# Proiect_TSC_v66.net
KiCad netlist of a schematic drawn in EAGLE
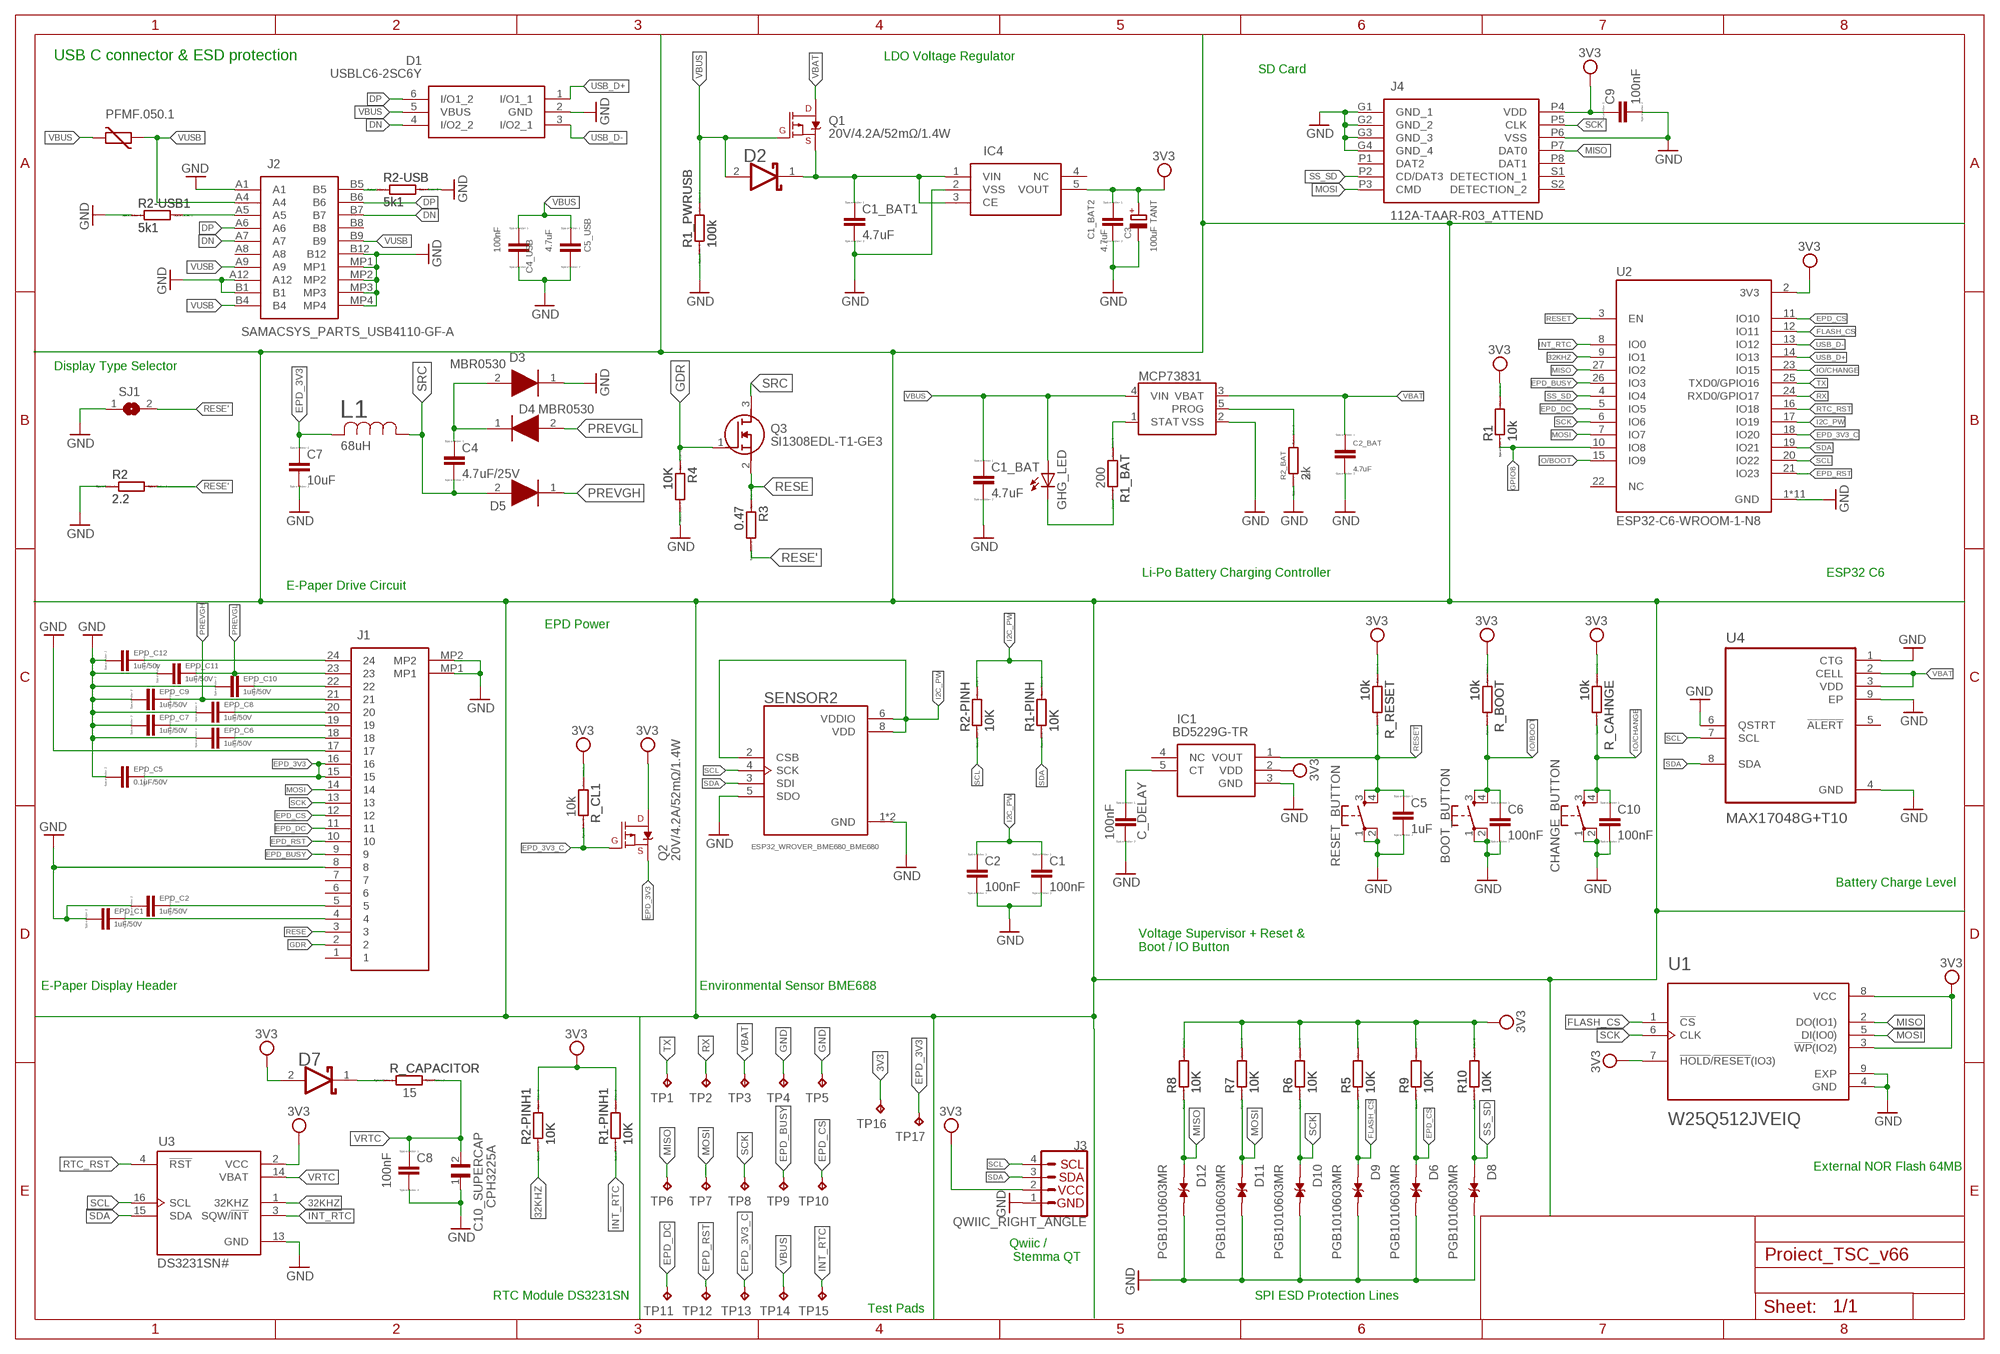
[diagram p0: schematic, sheet 1]

(export (version "E")
  (design (tool "Eeschema 10.0.6"))
  (components
    (comp (ref "BOOT_BUTTON")
      (value "BUTTON_CUSYOMV1")
      (footprint "eagle-import:MYBUTTON")
      (libsource (lib "eagle-import") (part "BUTTON_CUSYOMV1"))
    )
    (comp (ref "C1")
      (value "100nF")
      (footprint "eagle-import:EAGLE-LTSPICE_C0402")
      (libsource (lib "eagle-import") (part "EAGLE-LTSPICE_CC0402"))
    )
    (comp (ref "C1_BAT")
      (value "4.7uF")
      (footprint "eagle-import:ESP32_WROVER_EAGLE-LTSPICE_C0402")
      (libsource (lib "eagle-import") (part "ESP32_WROVER_EAGLE-LTSPICE_CC0402"))
    )
    (comp (ref "C1_BAT1")
      (value "4.7uF")
      (footprint "eagle-import:EAGLE-LTSPICE_C0402")
      (libsource (lib "eagle-import") (part "EAGLE-LTSPICE_CC0402"))
    )
    (comp (ref "C1_BAT2")
      (value "4.7uF")
      (footprint "eagle-import:EAGLE-LTSPICE_C0402")
      (libsource (lib "eagle-import") (part "EAGLE-LTSPICE_CC0402"))
    )
    (comp (ref "C2")
      (value "100nF")
      (footprint "eagle-import:EAGLE-LTSPICE_C0402")
      (libsource (lib "eagle-import") (part "EAGLE-LTSPICE_CC0402"))
    )
    (comp (ref "C2_BAT")
      (value "4.7uF")
      (footprint "eagle-import:ESP32_WROVER_EAGLE-LTSPICE_C0402")
      (libsource (lib "eagle-import") (part "ESP32_WROVER_EAGLE-LTSPICE_CC0402"))
    )
    (comp (ref "C3")
      (value "100uF TANT")
      (footprint "eagle-import:RCL_CT3528")
      (libsource (lib "eagle-import") (part "RCL_CPOL-EUCT3528"))
    )
    (comp (ref "C4")
      (value "4.7uF/25V")
      (footprint "eagle-import:ESP32_WROVER_EAGLE-LTSPICE_C0402")
      (libsource (lib "eagle-import") (part "ESP32_WROVER_EAGLE-LTSPICE_CC0402"))
    )
    (comp (ref "C4_USB")
      (value "100nF")
      (footprint "eagle-import:ESP32_WROVER_EAGLE-LTSPICE_C0402")
      (libsource (lib "eagle-import") (part "ESP32_WROVER_EAGLE-LTSPICE_CC0402"))
    )
    (comp (ref "C5")
      (value "1uF")
      (footprint "eagle-import:ESP32_WROVER_EAGLE-LTSPICE_C0402")
      (libsource (lib "eagle-import") (part "ESP32_WROVER_EAGLE-LTSPICE_CC0402"))
    )
    (comp (ref "C5_USB")
      (value "4.7uF")
      (footprint "eagle-import:ESP32_WROVER_EAGLE-LTSPICE_C0402")
      (libsource (lib "eagle-import") (part "ESP32_WROVER_EAGLE-LTSPICE_CC0402"))
    )
    (comp (ref "C6")
      (value "100nF")
      (footprint "eagle-import:ESP32_WROVER_EAGLE-LTSPICE_C0402")
      (libsource (lib "eagle-import") (part "ESP32_WROVER_EAGLE-LTSPICE_CC0402"))
    )
    (comp (ref "C7")
      (value "10uF")
      (footprint "eagle-import:EAGLE-LTSPICE_C0402")
      (libsource (lib "eagle-import") (part "EAGLE-LTSPICE_CC0402"))
    )
    (comp (ref "C8")
      (value "100nF")
      (footprint "eagle-import:ESP32_WROVER_EAGLE-LTSPICE_C0402")
      (libsource (lib "eagle-import") (part "ESP32_WROVER_EAGLE-LTSPICE_CC0402"))
    )
    (comp (ref "C9")
      (value "100nF")
      (footprint "eagle-import:EAGLE-LTSPICE_C0402")
      (libsource (lib "eagle-import") (part "EAGLE-LTSPICE_CC0402"))
    )
    (comp (ref "C10")
      (value "100nF")
      (footprint "eagle-import:ESP32_WROVER_EAGLE-LTSPICE_C0402")
      (libsource (lib "eagle-import") (part "ESP32_WROVER_EAGLE-LTSPICE_CC0402"))
    )
    (comp (ref "C10_SUPERCAP")
      (value "CPH3225A")
      (footprint "eagle-import:CAPCP3225X100N")
      (fields (field (name "MF") "Seiko Instruments"))
      (libsource (lib "eagle-import") (part "CPH3225A"))
    )
    (comp (ref "CHANGE_BUTTON")
      (value "BUTTON_CUSYOMV1")
      (footprint "eagle-import:MYBUTTON")
      (libsource (lib "eagle-import") (part "BUTTON_CUSYOMV1"))
    )
    (comp (ref "C_DELAY")
      (value "100nF")
      (footprint "eagle-import:EAGLE-LTSPICE_C0402")
      (libsource (lib "eagle-import") (part "EAGLE-LTSPICE_CC0402"))
    )
    (comp (ref "D1")
      (value "USBLC6-2SC6Y")
      (footprint "eagle-import:SOT95P280X145-6N")
      (fields (field (name "MF") "STMicroelectronics"))
      (libsource (lib "eagle-import") (part "USBLC6-2SC6Y"))
    )
    (comp (ref "D2")
      (value "ESP32_WROVER_AVX---SD0805S020S1R0_AVX_SD0805S020S1R0_0_0AVX_SD0805S020S1R0_0_0")
      (footprint "eagle-import:ESP32_WROVER_AVX---SD0805S020S1R0_AVX_SD0805S020S1R0_0")
      (fields
        (field (name "DIGIKEY_PART_NUMBER") "478-7800-1-ND")
        (field (name "MF") "AVX")
        (field (name "MOUSER_PART_NUMBER") "581-SD0805S020S1R0")
      )
      (libsource (lib "eagle-import") (part "ESP32_WROVER_AVX---SD0805S020S1R0_AVX_SD0805S020S1R0_0_0AVX_SD0805S020S1R0_0_0"))
    )
    (comp (ref "D3")
      (value "MBR0530")
      (footprint "eagle-import:SOD3716X135N")
      (fields (field (name "MF") "ON Semiconductor"))
      (libsource (lib "eagle-import") (part "MBR0530"))
    )
    (comp (ref "D4")
      (value "MBR0530")
      (footprint "eagle-import:SOD3716X135N")
      (fields (field (name "MF") "ON Semiconductor"))
      (libsource (lib "eagle-import") (part "MBR0530"))
    )
    (comp (ref "D5")
      (value "MBR0530")
      (footprint "eagle-import:SOD3716X135N")
      (fields (field (name "MF") "ON Semiconductor"))
      (libsource (lib "eagle-import") (part "MBR0530"))
    )
    (comp (ref "D6")
      (value "PGB1010603MR")
      (footprint "eagle-import:DIOC1608X36N")
      (fields (field (name "MF") "Littelfuse Inc."))
      (libsource (lib "eagle-import") (part "PGB1010603MR"))
    )
    (comp (ref "D7")
      (value "ESP32_WROVER_AVX---SD0805S020S1R0_AVX_SD0805S020S1R0_0_0AVX_SD0805S020S1R0_0_0")
      (footprint "eagle-import:ESP32_WROVER_AVX---SD0805S020S1R0_AVX_SD0805S020S1R0_0")
      (fields
        (field (name "DIGIKEY_PART_NUMBER") "478-7800-1-ND")
        (field (name "MF") "AVX")
        (field (name "MOUSER_PART_NUMBER") "581-SD0805S020S1R0")
      )
      (libsource (lib "eagle-import") (part "ESP32_WROVER_AVX---SD0805S020S1R0_AVX_SD0805S020S1R0_0_0AVX_SD0805S020S1R0_0_0"))
    )
    (comp (ref "D8")
      (value "PGB1010603MR")
      (footprint "eagle-import:DIOC1608X36N")
      (fields (field (name "MF") "Littelfuse Inc."))
      (libsource (lib "eagle-import") (part "PGB1010603MR"))
    )
    (comp (ref "D9")
      (value "PGB1010603MR")
      (footprint "eagle-import:DIOC1608X36N")
      (fields (field (name "MF") "Littelfuse Inc."))
      (libsource (lib "eagle-import") (part "PGB1010603MR"))
    )
    (comp (ref "D10")
      (value "PGB1010603MR")
      (footprint "eagle-import:DIOC1608X36N")
      (fields (field (name "MF") "Littelfuse Inc."))
      (libsource (lib "eagle-import") (part "PGB1010603MR"))
    )
    (comp (ref "D11")
      (value "PGB1010603MR")
      (footprint "eagle-import:DIOC1608X36N")
      (fields (field (name "MF") "Littelfuse Inc."))
      (libsource (lib "eagle-import") (part "PGB1010603MR"))
    )
    (comp (ref "D12")
      (value "PGB1010603MR")
      (footprint "eagle-import:DIOC1608X36N")
      (fields (field (name "MF") "Littelfuse Inc."))
      (libsource (lib "eagle-import") (part "PGB1010603MR"))
    )
    (comp (ref "EPD_C1")
      (value "1uF/50V")
      (footprint "eagle-import:EAGLE-LTSPICE_C0402")
      (libsource (lib "eagle-import") (part "EAGLE-LTSPICE_CC0402"))
    )
    (comp (ref "EPD_C2")
      (value "1uF/50V")
      (footprint "eagle-import:EAGLE-LTSPICE_C0402")
      (libsource (lib "eagle-import") (part "EAGLE-LTSPICE_CC0402"))
    )
    (comp (ref "EPD_C5")
      (value "0.1uF/50V")
      (footprint "eagle-import:EAGLE-LTSPICE_C0402")
      (libsource (lib "eagle-import") (part "EAGLE-LTSPICE_CC0402"))
    )
    (comp (ref "EPD_C6")
      (value "1uF/50V")
      (footprint "eagle-import:EAGLE-LTSPICE_C0402")
      (libsource (lib "eagle-import") (part "EAGLE-LTSPICE_CC0402"))
    )
    (comp (ref "EPD_C7")
      (value "1uF/50V")
      (footprint "eagle-import:EAGLE-LTSPICE_C0402")
      (libsource (lib "eagle-import") (part "EAGLE-LTSPICE_CC0402"))
    )
    (comp (ref "EPD_C8")
      (value "1uF/50V")
      (footprint "eagle-import:EAGLE-LTSPICE_C0402")
      (libsource (lib "eagle-import") (part "EAGLE-LTSPICE_CC0402"))
    )
    (comp (ref "EPD_C9")
      (value "1uF/50V")
      (footprint "eagle-import:EAGLE-LTSPICE_C0402")
      (libsource (lib "eagle-import") (part "EAGLE-LTSPICE_CC0402"))
    )
    (comp (ref "EPD_C10")
      (value "1uF/50V")
      (footprint "eagle-import:EAGLE-LTSPICE_C0402")
      (libsource (lib "eagle-import") (part "EAGLE-LTSPICE_CC0402"))
    )
    (comp (ref "EPD_C11")
      (value "1uF/50V")
      (footprint "eagle-import:EAGLE-LTSPICE_C0402")
      (libsource (lib "eagle-import") (part "EAGLE-LTSPICE_CC0402"))
    )
    (comp (ref "EPD_C12")
      (value "1uF/50v")
      (footprint "eagle-import:EAGLE-LTSPICE_C0402")
      (libsource (lib "eagle-import") (part "EAGLE-LTSPICE_CC0402"))
    )
    (comp (ref "GHG_LED")
      (value "ADAFRUIT_LEDCHIP-LED0603")
      (footprint "eagle-import:ADAFRUIT_CHIP-LED0603")
      (libsource (lib "eagle-import") (part "ADAFRUIT_LEDCHIP-LED0603"))
    )
    (comp (ref "IC1")
      (value "BD5229G-TR")
      (footprint "eagle-import:SOT95P280X125-5N")
      (fields (field (name "MOUSER_PART_NUMBER") "755-BD5229G-TR"))
      (libsource (lib "eagle-import") (part "BD5229G-TR"))
    )
    (comp (ref "IC4")
      (value "XC6220A331MR-G")
      (footprint "eagle-import:SOT95P280X120-5N")
      (fields (field (name "MOUSER_PART_NUMBER") "865-XC6220A331MR-G"))
      (libsource (lib "eagle-import") (part "XC6220A331MR-G"))
    )
    (comp (ref "J1")
      (value "FH34SRJ-24S-0.5SH_99_")
      (footprint "eagle-import:FH34SRJ24S05SH99")
      (fields
        (field (name "MANUFACTURER_PART_NUMBER") "FH34SRJ-24S-0.5SH(99)")
        (field (name "MOUSER_PART_NUMBER") "798-FH34SRJ24S05SH99")
      )
      (libsource (lib "eagle-import") (part "FH34SRJ-24S-0.5SH_99_"))
    )
    (comp (ref "J2")
      (value "SAMACSYS_PARTS_USB4110-GF-A")
      (footprint "eagle-import:SAMACSYS_PARTS_USB4110GFA")
      (fields
        (field (name "MANUFACTURER_PART_NUMBER") "USB4110-GF-A")
        (field (name "MOUSER_PART_NUMBER") "640-USB4110-GF-A")
      )
      (libsource (lib "eagle-import") (part "SAMACSYS_PARTS_USB4110-GF-A"))
    )
    (comp (ref "J3")
      (value "QWIIC_RIGHT_ANGLE")
      (footprint "eagle-import:JST04_1MM_RA")
      (libsource (lib "eagle-import") (part "QWIIC_CONNECTORJS-1MM"))
    )
    (comp (ref "J4")
      (value "112A-TAAR-R03_ATTEND")
      (footprint "eagle-import:112ATAARR03ATTEND")
      (fields (field (name "MANUFACTURER_PART_NUMBER") "112A-TAAR-R03 ATTEND"))
      (libsource (lib "eagle-import") (part "112A-TAAR-R03_ATTEND"))
    )
    (comp (ref "L1")
      (value "68uH")
      (footprint "eagle-import:IND_4828-WE-TPC_WRE")
      (fields
        (field (name "MANUFACTURER_PART_NUMBER") "744043680")
        (field (name "COPYRIGHT") "Copyright (C) 2024 Ultra Librarian. All rights reserved.")
      )
      (libsource (lib "eagle-import") (part "744043680IND_4828-WE-TPC_WRE"))
    )
    (comp (ref "MCP73831")
      (value "ESP32_WROVER_SPARKFUN-IC-POWER_MCP73831")
      (footprint "eagle-import:ESP32_WROVER_SPARKFUN-IC-POWER_SOT23-5")
      (libsource (lib "eagle-import") (part "ESP32_WROVER_SPARKFUN-IC-POWER_MCP73831"))
    )
    (comp (ref "PFMF.050.1")
      (value "ESP32C6_VARISTORCN1812")
      (footprint "eagle-import:ESP32C6_VARISTOR_CT_CN1812")
      (libsource (lib "eagle-import") (part "ESP32C6_VARISTORCN1812"))
    )
    (comp (ref "Q1")
      (value "20V/4.2A/52mΩ/1.4W")
      (footprint "eagle-import:ESP32_WROVER_SPARKFUN-DISCRETESEMI_SOT23-3")
      (libsource (lib "eagle-import") (part "ESP32_WROVER_SPARKFUN-DISCRETESEMI_MOSFET_PCH-DMG2305UX-7"))
    )
    (comp (ref "Q2")
      (value "20V/4.2A/52mΩ/1.4W")
      (footprint "eagle-import:ESP32_WROVER_SPARKFUN-DISCRETESEMI_SOT23-3")
      (libsource (lib "eagle-import") (part "ESP32_WROVER_SPARKFUN-DISCRETESEMI_MOSFET_PCH-DMG2305UX-7"))
    )
    (comp (ref "Q3")
      (value "SI1308EDL-T1-GE3")
      (footprint "eagle-import:SOT65P210X110-3N")
      (fields (field (name "MF") "Vishay Siliconix"))
      (libsource (lib "eagle-import") (part "SI1308EDL-T1-GE3"))
    )
    (comp (ref "R1")
      (value "10k")
      (footprint "eagle-import:ESP32_WROVER_EAGLE-LTSPICE_R0402")
      (libsource (lib "eagle-import") (part "ESP32_WROVER_EAGLE-LTSPICE_RR0402"))
    )
    (comp (ref "R1-PINH")
      (value "10K")
      (footprint "eagle-import:ESP32_WROVER_EAGLE-LTSPICE_R0402")
      (libsource (lib "eagle-import") (part "ESP32_WROVER_EAGLE-LTSPICE_RR0402"))
    )
    (comp (ref "R1-PINH1")
      (value "10K")
      (footprint "eagle-import:ESP32_WROVER_EAGLE-LTSPICE_R0402")
      (libsource (lib "eagle-import") (part "ESP32_WROVER_EAGLE-LTSPICE_RR0402"))
    )
    (comp (ref "R1_BAT")
      (value "200")
      (footprint "eagle-import:ESP32_WROVER_EAGLE-LTSPICE_R0402")
      (libsource (lib "eagle-import") (part "ESP32_WROVER_EAGLE-LTSPICE_RR0402"))
    )
    (comp (ref "R1_PWRUSB")
      (value "100k")
      (footprint "eagle-import:ESP32_WROVER_EAGLE-LTSPICE_R0402")
      (libsource (lib "eagle-import") (part "ESP32_WROVER_EAGLE-LTSPICE_RR0402"))
    )
    (comp (ref "R2")
      (value "2.2")
      (footprint "eagle-import:ESP32_WROVER_EAGLE-LTSPICE_R0402")
      (libsource (lib "eagle-import") (part "ESP32_WROVER_EAGLE-LTSPICE_RR0402"))
    )
    (comp (ref "R2-PINH")
      (value "10K")
      (footprint "eagle-import:ESP32_WROVER_EAGLE-LTSPICE_R0402")
      (libsource (lib "eagle-import") (part "ESP32_WROVER_EAGLE-LTSPICE_RR0402"))
    )
    (comp (ref "R2-PINH1")
      (value "10K")
      (footprint "eagle-import:ESP32_WROVER_EAGLE-LTSPICE_R0402")
      (libsource (lib "eagle-import") (part "ESP32_WROVER_EAGLE-LTSPICE_RR0402"))
    )
    (comp (ref "R2-USB")
      (value "5k1")
      (footprint "eagle-import:ESP32_WROVER_EAGLE-LTSPICE_R0402")
      (libsource (lib "eagle-import") (part "ESP32_WROVER_EAGLE-LTSPICE_RR0402"))
    )
    (comp (ref "R2-USB1")
      (value "5k1")
      (footprint "eagle-import:ESP32_WROVER_EAGLE-LTSPICE_R0402")
      (libsource (lib "eagle-import") (part "ESP32_WROVER_EAGLE-LTSPICE_RR0402"))
    )
    (comp (ref "R2_BAT")
      (value "2k")
      (footprint "eagle-import:ESP32_WROVER_EAGLE-LTSPICE_R0402")
      (libsource (lib "eagle-import") (part "ESP32_WROVER_EAGLE-LTSPICE_RR0402"))
    )
    (comp (ref "R3")
      (value "0.47")
      (footprint "eagle-import:ESP32_WROVER_EAGLE-LTSPICE_R0402")
      (libsource (lib "eagle-import") (part "ESP32_WROVER_EAGLE-LTSPICE_RR0402"))
    )
    (comp (ref "R4")
      (value "10K")
      (footprint "eagle-import:ESP32_WROVER_EAGLE-LTSPICE_R0402")
      (libsource (lib "eagle-import") (part "ESP32_WROVER_EAGLE-LTSPICE_RR0402"))
    )
    (comp (ref "R5")
      (value "10K")
      (footprint "eagle-import:ESP32_WROVER_EAGLE-LTSPICE_R0402")
      (libsource (lib "eagle-import") (part "ESP32_WROVER_EAGLE-LTSPICE_RR0402"))
    )
    (comp (ref "R6")
      (value "10K")
      (footprint "eagle-import:ESP32_WROVER_EAGLE-LTSPICE_R0402")
      (libsource (lib "eagle-import") (part "ESP32_WROVER_EAGLE-LTSPICE_RR0402"))
    )
    (comp (ref "R7")
      (value "10K")
      (footprint "eagle-import:ESP32_WROVER_EAGLE-LTSPICE_R0402")
      (libsource (lib "eagle-import") (part "ESP32_WROVER_EAGLE-LTSPICE_RR0402"))
    )
    (comp (ref "R8")
      (value "10K")
      (footprint "eagle-import:ESP32_WROVER_EAGLE-LTSPICE_R0402")
      (libsource (lib "eagle-import") (part "ESP32_WROVER_EAGLE-LTSPICE_RR0402"))
    )
    (comp (ref "R9")
      (value "10K")
      (footprint "eagle-import:ESP32_WROVER_EAGLE-LTSPICE_R0402")
      (libsource (lib "eagle-import") (part "ESP32_WROVER_EAGLE-LTSPICE_RR0402"))
    )
    (comp (ref "R10")
      (value "10K")
      (footprint "eagle-import:ESP32_WROVER_EAGLE-LTSPICE_R0402")
      (libsource (lib "eagle-import") (part "ESP32_WROVER_EAGLE-LTSPICE_RR0402"))
    )
    (comp (ref "RESET_BUTTON")
      (value "BUTTON_CUSYOMV1")
      (footprint "eagle-import:MYBUTTON")
      (libsource (lib "eagle-import") (part "BUTTON_CUSYOMV1"))
    )
    (comp (ref "R_BOOT")
      (value "10k")
      (footprint "eagle-import:ESP32_WROVER_EAGLE-LTSPICE_R0402")
      (libsource (lib "eagle-import") (part "ESP32_WROVER_EAGLE-LTSPICE_RR0402"))
    )
    (comp (ref "R_CAHNGE")
      (value "10k")
      (footprint "eagle-import:ESP32_WROVER_EAGLE-LTSPICE_R0402")
      (libsource (lib "eagle-import") (part "ESP32_WROVER_EAGLE-LTSPICE_RR0402"))
    )
    (comp (ref "R_CAPACITOR")
      (value "15")
      (footprint "eagle-import:ESP32_WROVER_EAGLE-LTSPICE_R0402")
      (libsource (lib "eagle-import") (part "ESP32_WROVER_EAGLE-LTSPICE_RR0402"))
    )
    (comp (ref "R_CL1")
      (value "10k")
      (footprint "eagle-import:ESP32_WROVER_EAGLE-LTSPICE_R0402")
      (libsource (lib "eagle-import") (part "ESP32_WROVER_EAGLE-LTSPICE_RR0402"))
    )
    (comp (ref "R_RESET")
      (value "10k")
      (footprint "eagle-import:ESP32_WROVER_EAGLE-LTSPICE_R0402")
      (libsource (lib "eagle-import") (part "ESP32_WROVER_EAGLE-LTSPICE_RR0402"))
    )
    (comp (ref "SENSOR2")
      (value "ESP32_WROVER_BME680_BME680")
      (footprint "eagle-import:ESP32_WROVER_BME680_PSON80P300X300X100-8N")
      (fields (field (name "MF") "Bosch Sensortec") (field (name "MP") "BME680"))
      (libsource (lib "eagle-import") (part "ESP32_WROVER_BME680_BME680"))
    )
    (comp (ref "SJ1") (value "SJ") (footprint "eagle-import:SJ") (libsource (lib "eagle-import") (part "SJ")))
    (comp (ref "TP1")
      (value "TPTP20R")
      (footprint "eagle-import:TP20R")
      (libsource (lib "eagle-import") (part "TPTP20R"))
    )
    (comp (ref "TP2")
      (value "TPTP20R")
      (footprint "eagle-import:TP20R")
      (libsource (lib "eagle-import") (part "TPTP20R"))
    )
    (comp (ref "TP3")
      (value "TPTP20R")
      (footprint "eagle-import:TP20R")
      (libsource (lib "eagle-import") (part "TPTP20R"))
    )
    (comp (ref "TP4")
      (value "TPTP20R")
      (footprint "eagle-import:TP20R")
      (libsource (lib "eagle-import") (part "TPTP20R"))
    )
    (comp (ref "TP5")
      (value "TPTP20R")
      (footprint "eagle-import:TP20R")
      (libsource (lib "eagle-import") (part "TPTP20R"))
    )
    (comp (ref "TP6")
      (value "TPTP20R")
      (footprint "eagle-import:TP20R")
      (libsource (lib "eagle-import") (part "TPTP20R"))
    )
    (comp (ref "TP7")
      (value "TPTP20R")
      (footprint "eagle-import:TP20R")
      (libsource (lib "eagle-import") (part "TPTP20R"))
    )
    (comp (ref "TP8")
      (value "TPTP20R")
      (footprint "eagle-import:TP20R")
      (libsource (lib "eagle-import") (part "TPTP20R"))
    )
    (comp (ref "TP9")
      (value "TPTP20R")
      (footprint "eagle-import:TP20R")
      (libsource (lib "eagle-import") (part "TPTP20R"))
    )
    (comp (ref "TP10")
      (value "TPTP20R")
      (footprint "eagle-import:TP20R")
      (libsource (lib "eagle-import") (part "TPTP20R"))
    )
    (comp (ref "TP11")
      (value "TPTP20R")
      (footprint "eagle-import:TP20R")
      (libsource (lib "eagle-import") (part "TPTP20R"))
    )
    (comp (ref "TP12")
      (value "TPTP20R")
      (footprint "eagle-import:TP20R")
      (libsource (lib "eagle-import") (part "TPTP20R"))
    )
    (comp (ref "TP13")
      (value "TPTP20R")
      (footprint "eagle-import:TP20R")
      (libsource (lib "eagle-import") (part "TPTP20R"))
    )
    (comp (ref "TP14")
      (value "TPTP20R")
      (footprint "eagle-import:TP20R")
      (libsource (lib "eagle-import") (part "TPTP20R"))
    )
    (comp (ref "TP15")
      (value "TPTP20R")
      (footprint "eagle-import:TP20R")
      (libsource (lib "eagle-import") (part "TPTP20R"))
    )
    (comp (ref "TP16")
      (value "TPTP20R")
      (footprint "eagle-import:TP20R")
      (libsource (lib "eagle-import") (part "TPTP20R"))
    )
    (comp (ref "TP17")
      (value "TPTP20R")
      (footprint "eagle-import:TP20R")
      (libsource (lib "eagle-import") (part "TPTP20R"))
    )
    (comp (ref "U1")
      (value "W25Q512JVEIQ")
      (footprint "eagle-import:SON127P600X800X80-9N")
      (fields (field (name "MF") "Winbond Electronics"))
      (libsource (lib "eagle-import") (part "W25Q512JVEIQ"))
    )
    (comp (ref "U2")
      (value "ESP32-C6-WROOM-1-N8")
      (footprint "eagle-import:XCVR_ESP32-C6-WROOM-1-N8")
      (fields (field (name "MF") "Espressif Systems"))
      (libsource (lib "eagle-import") (part "ESP32-C6-WROOM-1-N8"))
    )
    (comp (ref "U3")
      (value "DS3231SN#")
      (footprint "eagle-import:SOIC127P1032X265-16N")
      (fields (field (name "MF") "Analog Devices"))
      (libsource (lib "eagle-import") (part "DS3231SN#"))
    )
    (comp (ref "U4")
      (value "MAX17048G+T10")
      (footprint "eagle-import:SON50P200X200X80-9N")
      (fields (field (name "MF") "Analog Devices"))
      (libsource (lib "eagle-import") (part "MAX17048G+T10"))
    )
  )
  (nets
    (net (code "1") (name "3V3") (class "Default")
      (node (ref "C1_BAT2") (pin "1") (pinfunction "1_1") (pintype "passive"))
      (node (ref "C3") (pin "+") (pinfunction "+_+") (pintype "passive"))
      (node (ref "C9") (pin "1") (pinfunction "1_1") (pintype "passive"))
      (node (ref "D7") (pin "2") (pinfunction "ANODE_2") (pintype "bidirectional"))
      (node (ref "IC1") (pin "2") (pinfunction "VDD_2") (pintype "bidirectional"))
      (node (ref "IC4") (pin "5") (pinfunction "VOUT_5") (pintype "bidirectional"))
      (node (ref "J3") (pin "2") (pinfunction "2_2") (pintype "power_in"))
      (node (ref "J4") (pin "P4") (pinfunction "VDD_P4") (pintype "bidirectional"))
      (node (ref "Q2") (pin "3") (pinfunction "D_3") (pintype "bidirectional"))
      (node (ref "R1") (pin "2") (pinfunction "2_2") (pintype "passive"))
      (node (ref "R1-PINH1") (pin "2") (pinfunction "2_2") (pintype "passive"))
      (node (ref "R10") (pin "2") (pinfunction "2_2") (pintype "passive"))
      (node (ref "R2-PINH1") (pin "2") (pinfunction "2_2") (pintype "passive"))
      (node (ref "R5") (pin "2") (pinfunction "2_2") (pintype "passive"))
      (node (ref "R6") (pin "2") (pinfunction "2_2") (pintype "passive"))
      (node (ref "R7") (pin "2") (pinfunction "2_2") (pintype "passive"))
      (node (ref "R8") (pin "2") (pinfunction "2_2") (pintype "passive"))
      (node (ref "R9") (pin "2") (pinfunction "2_2") (pintype "passive"))
      (node (ref "R_BOOT") (pin "1") (pinfunction "1_1") (pintype "passive"))
      (node (ref "R_CAHNGE") (pin "1") (pinfunction "1_1") (pintype "passive"))
      (node (ref "R_CL1") (pin "1") (pinfunction "1_1") (pintype "passive"))
      (node (ref "R_RESET") (pin "1") (pinfunction "1_1") (pintype "passive"))
      (node (ref "TP16") (pin "TP") (pinfunction "TP_TP") (pintype "input"))
      (node (ref "U1") (pin "3") (pinfunction "~{WP}(IO2)_3") (pintype "bidirectional"))
      (node (ref "U1") (pin "7") (pinfunction "~{HOLD}/~{RESET}(IO3)_7") (pintype "bidirectional"))
      (node (ref "U1") (pin "8") (pinfunction "VCC_8") (pintype "power_in"))
      (node (ref "U2") (pin "2") (pinfunction "3V3_2") (pintype "power_in"))
      (node (ref "U3") (pin "2") (pinfunction "VCC_2") (pintype "power_in"))
    )
    (net (code "2") (name "32KHZ") (class "Default")
      (node (ref "R2-PINH1") (pin "1") (pinfunction "1_1") (pintype "passive"))
      (node (ref "U2") (pin "9") (pinfunction "IO1_9") (pintype "bidirectional"))
      (node (ref "U3") (pin "1") (pinfunction "32KHZ_1") (pintype "output"))
    )
    (net (code "3") (name "DN") (class "Default")
      (node (ref "D1") (pin "4") (pinfunction "I/O2_2_4") (pintype "bidirectional"))
      (node (ref "J2") (pin "A7") (pinfunction "A7_A7") (pintype "bidirectional"))
      (node (ref "J2") (pin "B7") (pinfunction "B7_B7") (pintype "bidirectional"))
    )
    (net (code "4") (name "DP") (class "Default")
      (node (ref "D1") (pin "6") (pinfunction "I/O1_2_6") (pintype "bidirectional"))
      (node (ref "J2") (pin "A6") (pinfunction "A6_A6") (pintype "bidirectional"))
      (node (ref "J2") (pin "B6") (pinfunction "B6_B6") (pintype "bidirectional"))
    )
    (net (code "5") (name "EPD_3V3") (class "Default")
      (node (ref "C7") (pin "1") (pinfunction "1_1") (pintype "passive"))
      (node (ref "EPD_C5") (pin "1") (pinfunction "1_1") (pintype "passive"))
      (node (ref "J1") (pin "15") (pinfunction "15_15") (pintype "bidirectional"))
      (node (ref "J1") (pin "16") (pinfunction "16_16") (pintype "bidirectional"))
      (node (ref "L1") (pin "2") (pinfunction "2_2") (pintype "passive"))
      (node (ref "Q2") (pin "2") (pinfunction "S_2") (pintype "bidirectional"))
      (node (ref "TP17") (pin "TP") (pinfunction "TP_TP") (pintype "input"))
    )
    (net (code "6") (name "EPD_3V3_C") (class "Default")
      (node (ref "Q2") (pin "1") (pinfunction "G_1") (pintype "bidirectional"))
      (node (ref "R_CL1") (pin "2") (pinfunction "2_2") (pintype "passive"))
      (node (ref "TP13") (pin "TP") (pinfunction "TP_TP") (pintype "input"))
      (node (ref "U2") (pin "18") (pinfunction "IO20_18") (pintype "bidirectional"))
    )
    (net (code "7") (name "EPD_BUSY") (class "Default")
      (node (ref "J1") (pin "9") (pinfunction "9_9") (pintype "bidirectional"))
      (node (ref "TP9") (pin "TP") (pinfunction "TP_TP") (pintype "input"))
      (node (ref "U2") (pin "26") (pinfunction "IO3_26") (pintype "bidirectional"))
    )
    (net (code "8") (name "EPD_CS") (class "Default")
      (node (ref "D6") (pin "1") (pinfunction "1_1") (pintype "passive"))
      (node (ref "J1") (pin "12") (pinfunction "12_12") (pintype "bidirectional"))
      (node (ref "R9") (pin "1") (pinfunction "1_1") (pintype "passive"))
      (node (ref "TP10") (pin "TP") (pinfunction "TP_TP") (pintype "input"))
      (node (ref "U2") (pin "11") (pinfunction "IO10_11") (pintype "bidirectional"))
    )
    (net (code "9") (name "EPD_DC") (class "Default")
      (node (ref "J1") (pin "11") (pinfunction "11_11") (pintype "bidirectional"))
      (node (ref "TP11") (pin "TP") (pinfunction "TP_TP") (pintype "input"))
      (node (ref "U2") (pin "5") (pinfunction "IO5_5") (pintype "bidirectional"))
    )
    (net (code "10") (name "EPD_RST") (class "Default")
      (node (ref "J1") (pin "10") (pinfunction "10_10") (pintype "bidirectional"))
      (node (ref "TP12") (pin "TP") (pinfunction "TP_TP") (pintype "input"))
      (node (ref "U2") (pin "21") (pinfunction "IO23_21") (pintype "bidirectional"))
    )
    (net (code "11") (name "FLASH_CS") (class "Default")
      (node (ref "D9") (pin "1") (pinfunction "1_1") (pintype "passive"))
      (node (ref "R5") (pin "1") (pinfunction "1_1") (pintype "passive"))
      (node (ref "U1") (pin "1") (pinfunction "~{CS}_1") (pintype "input"))
      (node (ref "U2") (pin "12") (pinfunction "IO11_12") (pintype "bidirectional"))
    )
    (net (code "12") (name "GDR") (class "Default")
      (node (ref "J1") (pin "2") (pinfunction "2_2") (pintype "bidirectional"))
      (node (ref "Q3") (pin "1") (pinfunction "G_1") (pintype "bidirectional"))
      (node (ref "R4") (pin "1") (pinfunction "1_1") (pintype "passive"))
    )
    (net (code "13") (name "GND") (class "Default")
      (node (ref "BOOT_BUTTON") (pin "1") (pinfunction "1_1") (pintype "passive"))
      (node (ref "BOOT_BUTTON") (pin "2") (pinfunction "2_2") (pintype "passive"))
      (node (ref "C1") (pin "2") (pinfunction "2_2") (pintype "passive"))
      (node (ref "C10") (pin "2") (pinfunction "2_2") (pintype "passive"))
      (node (ref "C10_SUPERCAP") (pin "1") (pinfunction "1_1") (pintype "passive"))
      (node (ref "C1_BAT") (pin "2") (pinfunction "2_2") (pintype "passive"))
      (node (ref "C1_BAT1") (pin "2") (pinfunction "2_2") (pintype "passive"))
      (node (ref "C1_BAT2") (pin "2") (pinfunction "2_2") (pintype "passive"))
      (node (ref "C2") (pin "2") (pinfunction "2_2") (pintype "passive"))
      (node (ref "C2_BAT") (pin "2") (pinfunction "2_2") (pintype "passive"))
      (node (ref "C3") (pin "-") (pinfunction "-_-") (pintype "passive"))
      (node (ref "C4_USB") (pin "2") (pinfunction "2_2") (pintype "passive"))
      (node (ref "C5") (pin "2") (pinfunction "2_2") (pintype "passive"))
      (node (ref "C5_USB") (pin "2") (pinfunction "2_2") (pintype "passive"))
      (node (ref "C6") (pin "2") (pinfunction "2_2") (pintype "passive"))
      (node (ref "C7") (pin "2") (pinfunction "2_2") (pintype "passive"))
      (node (ref "C8") (pin "2") (pinfunction "2_2") (pintype "passive"))
      (node (ref "C9") (pin "2") (pinfunction "2_2") (pintype "passive"))
      (node (ref "CHANGE_BUTTON") (pin "1") (pinfunction "1_1") (pintype "passive"))
      (node (ref "CHANGE_BUTTON") (pin "2") (pinfunction "2_2") (pintype "passive"))
      (node (ref "C_DELAY") (pin "2") (pinfunction "2_2") (pintype "passive"))
      (node (ref "D1") (pin "2") (pinfunction "GND_2") (pintype "bidirectional"))
      (node (ref "D10") (pin "2") (pinfunction "2_2") (pintype "passive"))
      (node (ref "D11") (pin "2") (pinfunction "2_2") (pintype "passive"))
      (node (ref "D12") (pin "2") (pinfunction "2_2") (pintype "passive"))
      (node (ref "D3") (pin "1") (pinfunction "K_1") (pintype "bidirectional"))
      (node (ref "D6") (pin "2") (pinfunction "2_2") (pintype "passive"))
      (node (ref "D8") (pin "2") (pinfunction "2_2") (pintype "passive"))
      (node (ref "D9") (pin "2") (pinfunction "2_2") (pintype "passive"))
      (node (ref "EPD_C1") (pin "2") (pinfunction "2_2") (pintype "passive"))
      (node (ref "EPD_C10") (pin "2") (pinfunction "2_2") (pintype "passive"))
      (node (ref "EPD_C11") (pin "2") (pinfunction "2_2") (pintype "passive"))
      (node (ref "EPD_C12") (pin "2") (pinfunction "2_2") (pintype "passive"))
      (node (ref "EPD_C2") (pin "2") (pinfunction "2_2") (pintype "passive"))
      (node (ref "EPD_C5") (pin "2") (pinfunction "2_2") (pintype "passive"))
      (node (ref "EPD_C6") (pin "2") (pinfunction "2_2") (pintype "passive"))
      (node (ref "EPD_C7") (pin "2") (pinfunction "2_2") (pintype "passive"))
      (node (ref "EPD_C8") (pin "2") (pinfunction "2_2") (pintype "passive"))
      (node (ref "EPD_C9") (pin "2") (pinfunction "2_2") (pintype "passive"))
      (node (ref "IC1") (pin "3") (pinfunction "GND_3") (pintype "bidirectional"))
      (node (ref "IC4") (pin "2") (pinfunction "VSS_2") (pintype "bidirectional"))
      (node (ref "J1") (pin "17") (pinfunction "17_17") (pintype "bidirectional"))
      (node (ref "J1") (pin "8") (pinfunction "8_8") (pintype "bidirectional"))
      (node (ref "J1") (pin "MP1") (pinfunction "MP1_MP1") (pintype "bidirectional"))
      (node (ref "J1") (pin "MP2") (pinfunction "MP2_MP2") (pintype "bidirectional"))
      (node (ref "J2") (pin "A1") (pinfunction "A1_A1") (pintype "bidirectional"))
      (node (ref "J2") (pin "A12") (pinfunction "A12_A12") (pintype "bidirectional"))
      (node (ref "J2") (pin "B1") (pinfunction "B1_B1") (pintype "bidirectional"))
      (node (ref "J2") (pin "B12") (pinfunction "B12_B12") (pintype "bidirectional"))
      (node (ref "J2") (pin "MP1") (pinfunction "MP1_MP1") (pintype "bidirectional"))
      (node (ref "J2") (pin "MP2") (pinfunction "MP2_MP2") (pintype "bidirectional"))
      (node (ref "J2") (pin "MP3") (pinfunction "MP3_MP3") (pintype "bidirectional"))
      (node (ref "J2") (pin "MP4") (pinfunction "MP4_MP4") (pintype "bidirectional"))
      (node (ref "J3") (pin "1") (pinfunction "1_1") (pintype "power_in"))
      (node (ref "J4") (pin "G1") (pinfunction "GND_1_G1") (pintype "bidirectional"))
      (node (ref "J4") (pin "G2") (pinfunction "GND_2_G2") (pintype "bidirectional"))
      (node (ref "J4") (pin "G3") (pinfunction "GND_3_G3") (pintype "bidirectional"))
      (node (ref "J4") (pin "G4") (pinfunction "GND_4_G4") (pintype "bidirectional"))
      (node (ref "J4") (pin "P6") (pinfunction "VSS_P6") (pintype "bidirectional"))
      (node (ref "MCP73831") (pin "2") (pinfunction "VSS_2") (pintype "power_in"))
      (node (ref "R1_PWRUSB") (pin "1") (pinfunction "1_1") (pintype "passive"))
      (node (ref "R2") (pin "1") (pinfunction "1_1") (pintype "passive"))
      (node (ref "R2-USB") (pin "2") (pinfunction "2_2") (pintype "passive"))
      (node (ref "R2-USB1") (pin "1") (pinfunction "1_1") (pintype "passive"))
      (node (ref "R2_BAT") (pin "1") (pinfunction "1_1") (pintype "passive"))
      (node (ref "R4") (pin "2") (pinfunction "2_2") (pintype "passive"))
      (node (ref "RESET_BUTTON") (pin "1") (pinfunction "1_1") (pintype "passive"))
      (node (ref "RESET_BUTTON") (pin "2") (pinfunction "2_2") (pintype "passive"))
      (node (ref "SENSOR2") (pin "1") (pinfunction "GND_1") (pintype "power_in"))
      (node (ref "SENSOR2") (pin "5") (pinfunction "SDO_5") (pintype "bidirectional"))
      (node (ref "SENSOR2") (pin "7") (pinfunction "GND_7") (pintype "power_in"))
      (node (ref "SJ1") (pin "1") (pinfunction "1_1") (pintype "passive"))
      (node (ref "TP4") (pin "TP") (pinfunction "TP_TP") (pintype "input"))
      (node (ref "TP5") (pin "TP") (pinfunction "TP_TP") (pintype "input"))
      (node (ref "U1") (pin "4") (pinfunction "GND_4") (pintype "power_in"))
      (node (ref "U1") (pin "9") (pinfunction "EXP_9") (pintype "passive"))
      (node (ref "U2") (pin "1") (pinfunction "GND_1") (pintype "power_in"))
      (node (ref "U2") (pin "28") (pinfunction "GND_28") (pintype "power_in"))
      (node (ref "U2") (pin "29_1") (pinfunction "GND_29_1") (pintype "power_in"))
      (node (ref "U2") (pin "29_2") (pinfunction "GND_29_2") (pintype "power_in"))
      (node (ref "U2") (pin "29_3") (pinfunction "GND_29_3") (pintype "power_in"))
      (node (ref "U2") (pin "29_4") (pinfunction "GND_29_4") (pintype "power_in"))
      (node (ref "U2") (pin "29_5") (pinfunction "GND_29_5") (pintype "power_in"))
      (node (ref "U2") (pin "29_6") (pinfunction "GND_29_6") (pintype "power_in"))
      (node (ref "U2") (pin "29_7") (pinfunction "GND_29_7") (pintype "power_in"))
      (node (ref "U2") (pin "29_8") (pinfunction "GND_29_8") (pintype "power_in"))
      (node (ref "U2") (pin "29_9") (pinfunction "GND_29_9") (pintype "power_in"))
      (node (ref "U3") (pin "13") (pinfunction "GND_13") (pintype "power_in"))
      (node (ref "U4") (pin "1") (pinfunction "CTG_1") (pintype "power_in"))
      (node (ref "U4") (pin "4") (pinfunction "GND_4") (pintype "power_in"))
      (node (ref "U4") (pin "6") (pinfunction "QSTRT_6") (pintype "input"))
      (node (ref "U4") (pin "9") (pinfunction "EP_9") (pintype "power_in"))
    )
    (net (code "14") (name "GPIO8") (class "Default")
      (node (ref "R1") (pin "1") (pinfunction "1_1") (pintype "passive"))
      (node (ref "U2") (pin "10") (pinfunction "IO8_10") (pintype "bidirectional"))
    )
    (net (code "15") (name "I2C_PW") (class "Default")
      (node (ref "C1") (pin "1") (pinfunction "1_1") (pintype "passive"))
      (node (ref "C2") (pin "1") (pinfunction "1_1") (pintype "passive"))
      (node (ref "R1-PINH") (pin "2") (pinfunction "2_2") (pintype "passive"))
      (node (ref "R2-PINH") (pin "2") (pinfunction "2_2") (pintype "passive"))
      (node (ref "SENSOR2") (pin "2") (pinfunction "CSB_2") (pintype "input"))
      (node (ref "SENSOR2") (pin "6") (pinfunction "VDDIO_6") (pintype "power_in"))
      (node (ref "SENSOR2") (pin "8") (pinfunction "VDD_8") (pintype "power_in"))
      (node (ref "U2") (pin "17") (pinfunction "IO19_17") (pintype "bidirectional"))
    )
    (net (code "16") (name "INT_RTC") (class "Default")
      (node (ref "R1-PINH1") (pin "1") (pinfunction "1_1") (pintype "passive"))
      (node (ref "TP15") (pin "TP") (pinfunction "TP_TP") (pintype "input"))
      (node (ref "U2") (pin "8") (pinfunction "IO0_8") (pintype "bidirectional"))
      (node (ref "U3") (pin "3") (pinfunction "SQW/~{INT}_3") (pintype "output"))
    )
    (net (code "17") (name "IO{slash}BOOT") (class "Default")
      (node (ref "BOOT_BUTTON") (pin "3") (pinfunction "3_3") (pintype "passive"))
      (node (ref "BOOT_BUTTON") (pin "4") (pinfunction "4_4") (pintype "passive"))
      (node (ref "C6") (pin "1") (pinfunction "1_1") (pintype "passive"))
      (node (ref "R_BOOT") (pin "2") (pinfunction "2_2") (pintype "passive"))
      (node (ref "U2") (pin "15") (pinfunction "IO9_15") (pintype "bidirectional"))
    )
    (net (code "18") (name "IO{slash}CHANGE") (class "Default")
      (node (ref "C10") (pin "1") (pinfunction "1_1") (pintype "passive"))
      (node (ref "CHANGE_BUTTON") (pin "3") (pinfunction "3_3") (pintype "passive"))
      (node (ref "CHANGE_BUTTON") (pin "4") (pinfunction "4_4") (pintype "passive"))
      (node (ref "R_CAHNGE") (pin "2") (pinfunction "2_2") (pintype "passive"))
      (node (ref "U2") (pin "23") (pinfunction "IO15_23") (pintype "bidirectional"))
    )
    (net (code "19") (name "MISO") (class "Default")
      (node (ref "D12") (pin "1") (pinfunction "1_1") (pintype "passive"))
      (node (ref "J4") (pin "P7") (pinfunction "DAT0_P7") (pintype "bidirectional"))
      (node (ref "R8") (pin "1") (pinfunction "1_1") (pintype "passive"))
      (node (ref "TP6") (pin "TP") (pinfunction "TP_TP") (pintype "input"))
      (node (ref "U1") (pin "2") (pinfunction "DO(IO1)_2") (pintype "bidirectional"))
      (node (ref "U2") (pin "27") (pinfunction "IO2_27") (pintype "bidirectional"))
    )
    (net (code "20") (name "MOSI") (class "Default")
      (node (ref "D11") (pin "1") (pinfunction "1_1") (pintype "passive"))
      (node (ref "J1") (pin "14") (pinfunction "14_14") (pintype "bidirectional"))
      (node (ref "J4") (pin "P3") (pinfunction "CMD_P3") (pintype "bidirectional"))
      (node (ref "R7") (pin "1") (pinfunction "1_1") (pintype "passive"))
      (node (ref "TP7") (pin "TP") (pinfunction "TP_TP") (pintype "input"))
      (node (ref "U1") (pin "5") (pinfunction "DI(IO0)_5") (pintype "bidirectional"))
      (node (ref "U2") (pin "7") (pinfunction "IO7_7") (pintype "bidirectional"))
    )
    (net (code "21") (name "Net-(D2-CATHODE)") (class "Default")
      (node (ref "C1_BAT1") (pin "1") (pinfunction "1_1") (pintype "passive"))
      (node (ref "D2") (pin "1") (pinfunction "CATHODE_1") (pintype "bidirectional"))
      (node (ref "IC4") (pin "1") (pinfunction "VIN_1") (pintype "bidirectional"))
      (node (ref "IC4") (pin "3") (pinfunction "CE_3") (pintype "bidirectional"))
      (node (ref "Q1") (pin "2") (pinfunction "S_2") (pintype "bidirectional"))
    )
    (net (code "22") (name "Net-(D3-A)") (class "Default")
      (node (ref "C4") (pin "1") (pinfunction "1_1") (pintype "passive"))
      (node (ref "D3") (pin "2") (pinfunction "A_2") (pintype "bidirectional"))
      (node (ref "D4") (pin "1") (pinfunction "K_1") (pintype "bidirectional"))
    )
    (net (code "23") (name "Net-(D7-CATHODE)") (class "Default")
      (node (ref "D7") (pin "1") (pinfunction "CATHODE_1") (pintype "bidirectional"))
      (node (ref "R_CAPACITOR") (pin "1") (pinfunction "1_1") (pintype "passive"))
    )
    (net (code "24") (name "Net-(EPD_C1-Pad1)") (class "Default")
      (node (ref "EPD_C1") (pin "1") (pinfunction "1_1") (pintype "passive"))
      (node (ref "J1") (pin "4") (pinfunction "4_4") (pintype "bidirectional"))
    )
    (net (code "25") (name "Net-(EPD_C2-Pad1)") (class "Default")
      (node (ref "EPD_C2") (pin "1") (pinfunction "1_1") (pintype "passive"))
      (node (ref "J1") (pin "5") (pinfunction "5_5") (pintype "bidirectional"))
    )
    (net (code "26") (name "Net-(EPD_C6-Pad1)") (class "Default")
      (node (ref "EPD_C6") (pin "1") (pinfunction "1_1") (pintype "passive"))
      (node (ref "J1") (pin "18") (pinfunction "18_18") (pintype "bidirectional"))
    )
    (net (code "27") (name "Net-(EPD_C7-Pad1)") (class "Default")
      (node (ref "EPD_C7") (pin "1") (pinfunction "1_1") (pintype "passive"))
      (node (ref "J1") (pin "19") (pinfunction "19_19") (pintype "bidirectional"))
    )
    (net (code "28") (name "Net-(EPD_C8-Pad1)") (class "Default")
      (node (ref "EPD_C8") (pin "1") (pinfunction "1_1") (pintype "passive"))
      (node (ref "J1") (pin "20") (pinfunction "20_20") (pintype "bidirectional"))
    )
    (net (code "29") (name "Net-(EPD_C10-Pad1)") (class "Default")
      (node (ref "EPD_C10") (pin "1") (pinfunction "1_1") (pintype "passive"))
      (node (ref "J1") (pin "22") (pinfunction "22_22") (pintype "bidirectional"))
    )
    (net (code "30") (name "Net-(EPD_C12-Pad1)") (class "Default")
      (node (ref "EPD_C12") (pin "1") (pinfunction "1_1") (pintype "passive"))
      (node (ref "J1") (pin "24") (pinfunction "24_24") (pintype "bidirectional"))
    )
    (net (code "31") (name "Net-(GHG_LED-PadC)") (class "Default")
      (node (ref "GHG_LED") (pin "C") (pinfunction "C_C") (pintype "passive"))
      (node (ref "R1_BAT") (pin "2") (pinfunction "2_2") (pintype "passive"))
    )
    (net (code "32") (name "Net-(IC1-CT)") (class "Default")
      (node (ref "C_DELAY") (pin "1") (pinfunction "1_1") (pintype "passive"))
      (node (ref "IC1") (pin "5") (pinfunction "CT_5") (pintype "bidirectional"))
    )
    (net (code "33") (name "Net-(J2-PadA5)") (class "Default")
      (node (ref "J2") (pin "A5") (pinfunction "A5_A5") (pintype "bidirectional"))
      (node (ref "R2-USB1") (pin "2") (pinfunction "2_2") (pintype "passive"))
    )
    (net (code "34") (name "Net-(J2-PadB5)") (class "Default")
      (node (ref "J2") (pin "B5") (pinfunction "B5_B5") (pintype "bidirectional"))
      (node (ref "R2-USB") (pin "1") (pinfunction "1_1") (pintype "passive"))
    )
    (net (code "35") (name "Net-(MCP73831-PROG)") (class "Default")
      (node (ref "MCP73831") (pin "5") (pinfunction "PROG_5") (pintype "input"))
      (node (ref "R2_BAT") (pin "2") (pinfunction "2_2") (pintype "passive"))
    )
    (net (code "36") (name "Net-(MCP73831-STAT)") (class "Default")
      (node (ref "MCP73831") (pin "1") (pinfunction "STAT_1") (pintype "output"))
      (node (ref "R1_BAT") (pin "1") (pinfunction "1_1") (pintype "passive"))
    )
    (net (code "37") (name "PREVGH") (class "Default")
      (node (ref "D5") (pin "1") (pinfunction "K_1") (pintype "bidirectional"))
      (node (ref "EPD_C9") (pin "1") (pinfunction "1_1") (pintype "passive"))
      (node (ref "J1") (pin "21") (pinfunction "21_21") (pintype "bidirectional"))
    )
    (net (code "38") (name "PREVGL") (class "Default")
      (node (ref "D4") (pin "2") (pinfunction "A_2") (pintype "bidirectional"))
      (node (ref "EPD_C11") (pin "1") (pinfunction "1_1") (pintype "passive"))
      (node (ref "J1") (pin "23") (pinfunction "23_23") (pintype "bidirectional"))
    )
    (net (code "39") (name "RESE") (class "Default")
      (node (ref "J1") (pin "3") (pinfunction "3_3") (pintype "bidirectional"))
      (node (ref "Q3") (pin "2") (pinfunction "S_2") (pintype "bidirectional"))
      (node (ref "R3") (pin "1") (pinfunction "1_1") (pintype "passive"))
    )
    (net (code "40") (name "RESE'") (class "Default")
      (node (ref "R2") (pin "2") (pinfunction "2_2") (pintype "passive"))
      (node (ref "R3") (pin "2") (pinfunction "2_2") (pintype "passive"))
      (node (ref "SJ1") (pin "2") (pinfunction "2_2") (pintype "passive"))
    )
    (net (code "41") (name "RESET") (class "Default")
      (node (ref "C5") (pin "1") (pinfunction "1_1") (pintype "passive"))
      (node (ref "IC1") (pin "1") (pinfunction "VOUT_1") (pintype "bidirectional"))
      (node (ref "RESET_BUTTON") (pin "3") (pinfunction "3_3") (pintype "passive"))
      (node (ref "RESET_BUTTON") (pin "4") (pinfunction "4_4") (pintype "passive"))
      (node (ref "R_RESET") (pin "2") (pinfunction "2_2") (pintype "passive"))
      (node (ref "U2") (pin "3") (pinfunction "EN_3") (pintype "input"))
    )
    (net (code "42") (name "RTC_RST") (class "Default")
      (node (ref "U2") (pin "16") (pinfunction "IO18_16") (pintype "bidirectional"))
      (node (ref "U3") (pin "4") (pinfunction "~{RST}_4") (pintype "input"))
    )
    (net (code "43") (name "RX") (class "Default")
      (node (ref "TP2") (pin "TP") (pinfunction "TP_TP") (pintype "input"))
      (node (ref "U2") (pin "24") (pinfunction "RXD0/GPIO17_24") (pintype "bidirectional"))
    )
    (net (code "44") (name "SCK") (class "Default")
      (node (ref "D10") (pin "1") (pinfunction "1_1") (pintype "passive"))
      (node (ref "J1") (pin "13") (pinfunction "13_13") (pintype "bidirectional"))
      (node (ref "J4") (pin "P5") (pinfunction "CLK_P5") (pintype "bidirectional"))
      (node (ref "R6") (pin "1") (pinfunction "1_1") (pintype "passive"))
      (node (ref "TP8") (pin "TP") (pinfunction "TP_TP") (pintype "input"))
      (node (ref "U1") (pin "6") (pinfunction "CLK_6") (pintype "input"))
      (node (ref "U2") (pin "6") (pinfunction "IO6_6") (pintype "bidirectional"))
    )
    (net (code "45") (name "SCL") (class "Default")
      (node (ref "J3") (pin "4") (pinfunction "4_4") (pintype "passive"))
      (node (ref "R2-PINH") (pin "1") (pinfunction "1_1") (pintype "passive"))
      (node (ref "SENSOR2") (pin "4") (pinfunction "SCK_4") (pintype "input"))
      (node (ref "U2") (pin "20") (pinfunction "IO22_20") (pintype "bidirectional"))
      (node (ref "U3") (pin "16") (pinfunction "SCL_16") (pintype "input"))
      (node (ref "U4") (pin "7") (pinfunction "SCL_7") (pintype "input"))
    )
    (net (code "46") (name "SDA") (class "Default")
      (node (ref "J3") (pin "3") (pinfunction "3_3") (pintype "passive"))
      (node (ref "R1-PINH") (pin "1") (pinfunction "1_1") (pintype "passive"))
      (node (ref "SENSOR2") (pin "3") (pinfunction "SDI_3") (pintype "bidirectional"))
      (node (ref "U2") (pin "19") (pinfunction "IO21_19") (pintype "bidirectional"))
      (node (ref "U3") (pin "15") (pinfunction "SDA_15") (pintype "bidirectional"))
      (node (ref "U4") (pin "8") (pinfunction "SDA_8") (pintype "bidirectional"))
    )
    (net (code "47") (name "SRC") (class "Default")
      (node (ref "C4") (pin "2") (pinfunction "2_2") (pintype "passive"))
      (node (ref "D5") (pin "2") (pinfunction "A_2") (pintype "bidirectional"))
      (node (ref "L1") (pin "1") (pinfunction "1_1") (pintype "passive"))
      (node (ref "Q3") (pin "3") (pinfunction "D_3") (pintype "bidirectional"))
    )
    (net (code "48") (name "SS_SD") (class "Default")
      (node (ref "D8") (pin "1") (pinfunction "1_1") (pintype "passive"))
      (node (ref "J4") (pin "P2") (pinfunction "CD/DAT3_P2") (pintype "bidirectional"))
      (node (ref "R10") (pin "1") (pinfunction "1_1") (pintype "passive"))
      (node (ref "U2") (pin "4") (pinfunction "IO4_4") (pintype "bidirectional"))
    )
    (net (code "49") (name "TX") (class "Default")
      (node (ref "TP1") (pin "TP") (pinfunction "TP_TP") (pintype "input"))
      (node (ref "U2") (pin "25") (pinfunction "TXD0/GPIO16_25") (pintype "bidirectional"))
    )
    (net (code "50") (name "USB_D+") (class "Default")
      (node (ref "D1") (pin "1") (pinfunction "I/O1_1_1") (pintype "bidirectional"))
      (node (ref "U2") (pin "14") (pinfunction "IO13_14") (pintype "bidirectional"))
    )
    (net (code "51") (name "USB_D-") (class "Default")
      (node (ref "D1") (pin "3") (pinfunction "I/O2_1_3") (pintype "bidirectional"))
      (node (ref "U2") (pin "13") (pinfunction "IO12_13") (pintype "bidirectional"))
    )
    (net (code "52") (name "VBAT") (class "Default")
      (node (ref "C2_BAT") (pin "1") (pinfunction "1_1") (pintype "passive"))
      (node (ref "MCP73831") (pin "3") (pinfunction "VBAT_3") (pintype "power_in"))
      (node (ref "Q1") (pin "3") (pinfunction "D_3") (pintype "bidirectional"))
      (node (ref "TP3") (pin "TP") (pinfunction "TP_TP") (pintype "input"))
      (node (ref "U4") (pin "2") (pinfunction "CELL_2") (pintype "power_in"))
      (node (ref "U4") (pin "3") (pinfunction "VDD_3") (pintype "power_in"))
    )
    (net (code "53") (name "VBUS") (class "Default")
      (node (ref "C1_BAT") (pin "1") (pinfunction "1_1") (pintype "passive"))
      (node (ref "C4_USB") (pin "1") (pinfunction "1_1") (pintype "passive"))
      (node (ref "C5_USB") (pin "1") (pinfunction "1_1") (pintype "passive"))
      (node (ref "D1") (pin "5") (pinfunction "VBUS_5") (pintype "bidirectional"))
      (node (ref "D2") (pin "2") (pinfunction "ANODE_2") (pintype "bidirectional"))
      (node (ref "GHG_LED") (pin "A") (pinfunction "A_A") (pintype "passive"))
      (node (ref "MCP73831") (pin "4") (pinfunction "VIN_4") (pintype "power_in"))
      (node (ref "PFMF.050.1") (pin "2") (pinfunction "2_2") (pintype "passive"))
      (node (ref "Q1") (pin "1") (pinfunction "G_1") (pintype "bidirectional"))
      (node (ref "R1_PWRUSB") (pin "2") (pinfunction "2_2") (pintype "passive"))
      (node (ref "TP14") (pin "TP") (pinfunction "TP_TP") (pintype "input"))
    )
    (net (code "54") (name "VRTC") (class "Default")
      (node (ref "C10_SUPERCAP") (pin "2") (pinfunction "2_2") (pintype "passive"))
      (node (ref "C8") (pin "1") (pinfunction "1_1") (pintype "passive"))
      (node (ref "R_CAPACITOR") (pin "2") (pinfunction "2_2") (pintype "passive"))
      (node (ref "U3") (pin "14") (pinfunction "VBAT_14") (pintype "power_in"))
    )
    (net (code "55") (name "VUSB") (class "Default")
      (node (ref "J2") (pin "A4") (pinfunction "A4_A4") (pintype "bidirectional"))
      (node (ref "J2") (pin "A9") (pinfunction "A9_A9") (pintype "bidirectional"))
      (node (ref "J2") (pin "B4") (pinfunction "B4_B4") (pintype "bidirectional"))
      (node (ref "J2") (pin "B9") (pinfunction "B9_B9") (pintype "bidirectional"))
      (node (ref "PFMF.050.1") (pin "1") (pinfunction "1_1") (pintype "passive"))
    )
    (net (code "56") (name "unconnected-(IC1-NC-Pad4)") (class "Default")
      (node (ref "IC1") (pin "4") (pinfunction "NC_4") (pintype "no_connect"))
    )
    (net (code "57") (name "unconnected-(IC4-NC-Pad4)") (class "Default")
      (node (ref "IC4") (pin "4") (pinfunction "NC_4") (pintype "no_connect"))
    )
    (net (code "58") (name "unconnected-(J1-Pad1)") (class "Default")
      (node (ref "J1") (pin "1") (pinfunction "1_1") (pintype "bidirectional"))
    )
    (net (code "59") (name "unconnected-(J1-Pad6)") (class "Default")
      (node (ref "J1") (pin "6") (pinfunction "6_6") (pintype "bidirectional"))
    )
    (net (code "60") (name "unconnected-(J1-Pad7)") (class "Default")
      (node (ref "J1") (pin "7") (pinfunction "7_7") (pintype "bidirectional"))
    )
    (net (code "61") (name "unconnected-(J2-PadA8)") (class "Default")
      (node (ref "J2") (pin "A8") (pinfunction "A8_A8") (pintype "bidirectional"))
    )
    (net (code "62") (name "unconnected-(J2-PadB8)") (class "Default")
      (node (ref "J2") (pin "B8") (pinfunction "B8_B8") (pintype "bidirectional"))
    )
    (net (code "63") (name "unconnected-(J4-DAT1-PadP8)") (class "Default")
      (node (ref "J4") (pin "P8") (pinfunction "DAT1_P8") (pintype "bidirectional"))
    )
    (net (code "64") (name "unconnected-(J4-DAT2-PadP1)") (class "Default")
      (node (ref "J4") (pin "P1") (pinfunction "DAT2_P1") (pintype "bidirectional"))
    )
    (net (code "65") (name "unconnected-(J4-DETECTION_1-PadS1)") (class "Default")
      (node (ref "J4") (pin "S1") (pinfunction "DETECTION_1_S1") (pintype "bidirectional"))
    )
    (net (code "66") (name "unconnected-(J4-DETECTION_2-PadS2)") (class "Default")
      (node (ref "J4") (pin "S2") (pinfunction "DETECTION_2_S2") (pintype "bidirectional"))
    )
    (net (code "67") (name "unconnected-(U2-NC-Pad22)") (class "Default")
      (node (ref "U2") (pin "22") (pinfunction "NC_22") (pintype "no_connect"))
    )
    (net (code "68") (name "unconnected-(U4-~{ALERT}-Pad5)") (class "Default")
      (node (ref "U4") (pin "5") (pinfunction "~{ALERT}_5") (pintype "output"))
    )
  )
)
